# Footswitches.net
KiCad netlist of a schematic drawn in Altium Designer
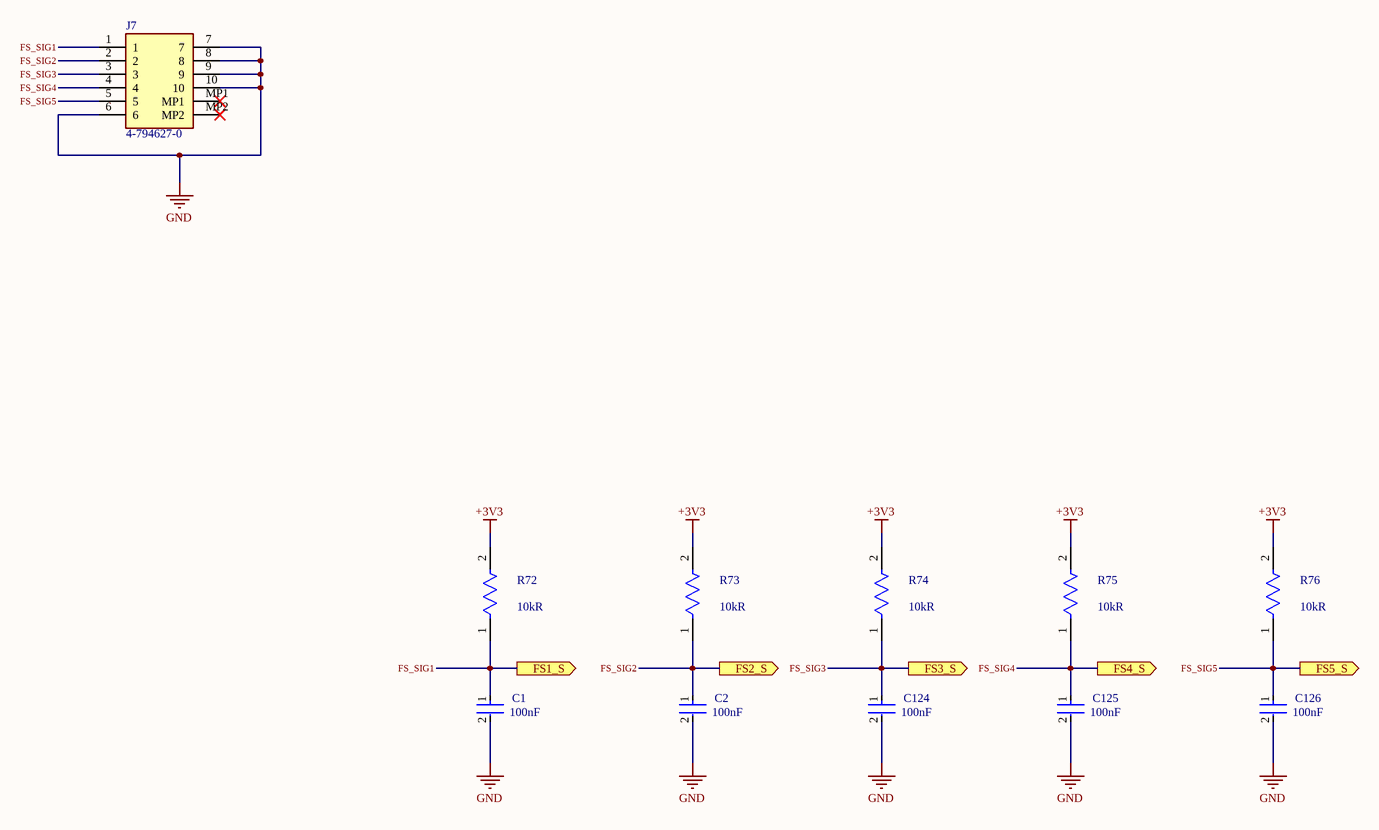
[diagram p0: Footswitches.SchDoc]

(export (version "E")
  (design (tool "Eeschema 10.0.6"))
  (components
    (comp (ref "C1")
      (value "GCM155R71H104ME02J")
      (footprint "FP-GCM155-0_05-IPC_A")
      (description "Ceramic Capacitor for Automotive 100nF ±20% 50VDC X7R 0402 Paper T/R")
      (fields (field (name "CAPACITANCE") "100nF"))
      (libsource (lib "Altium Content Vault") (part "02cd4be3c70576c341d710602a673aa"))
    )
    (comp (ref "C2")
      (value "GCM155R71H104ME02J")
      (footprint "FP-GCM155-0_05-IPC_A")
      (description "Ceramic Capacitor for Automotive 100nF ±20% 50VDC X7R 0402 Paper T/R")
      (fields (field (name "CAPACITANCE") "100nF"))
      (libsource (lib "Altium Content Vault") (part "02cd4be3c70576c341d710602a673aa"))
    )
    (comp (ref "C124")
      (value "GCM155R71H104ME02J")
      (footprint "FP-GCM155-0_05-IPC_A")
      (description "Ceramic Capacitor for Automotive 100nF ±20% 50VDC X7R 0402 Paper T/R")
      (fields (field (name "CAPACITANCE") "100nF"))
      (libsource (lib "Altium Content Vault") (part "02cd4be3c70576c341d710602a673aa"))
    )
    (comp (ref "C125")
      (value "GCM155R71H104ME02J")
      (footprint "FP-GCM155-0_05-IPC_A")
      (description "Ceramic Capacitor for Automotive 100nF ±20% 50VDC X7R 0402 Paper T/R")
      (fields (field (name "CAPACITANCE") "100nF"))
      (libsource (lib "Altium Content Vault") (part "02cd4be3c70576c341d710602a673aa"))
    )
    (comp (ref "C126")
      (value "GCM155R71H104ME02J")
      (footprint "FP-GCM155-0_05-IPC_A")
      (description "Ceramic Capacitor for Automotive 100nF ±20% 50VDC X7R 0402 Paper T/R")
      (fields (field (name "CAPACITANCE") "100nF"))
      (libsource (lib "Altium Content Vault") (part "02cd4be3c70576c341d710602a673aa"))
    )
    (comp (ref "J7")
      (value "4-794627-0")
      (footprint "SamacSys:47946270")
      (description "Connector")
      (fields (field (name "MOUSER PART NUMBER") "571-4-794627-0"))
      (libsource (lib "*") (part "4-794627-0"))
    )
    (comp (ref "R72")
      (value "RC0402FR-1310KL")
      (footprint "FP-RC0402-0_4-IPC_A")
      (description "RESISTOR 0402 10K 1%")
      (fields (field (name "RESISTANCE") "10kR") (field (name "TOLERANCE") "1%"))
      (libsource (lib "Altium Content Vault") (part "1029c3af85768c4190bb7ad29bc67b5"))
    )
    (comp (ref "R73")
      (value "RC0402FR-1310KL")
      (footprint "FP-RC0402-0_4-IPC_A")
      (description "RESISTOR 0402 10K 1%")
      (fields (field (name "RESISTANCE") "10kR") (field (name "TOLERANCE") "1%"))
      (libsource (lib "Altium Content Vault") (part "1029c3af85768c4190bb7ad29bc67b5"))
    )
    (comp (ref "R74")
      (value "RC0402FR-1310KL")
      (footprint "FP-RC0402-0_4-IPC_A")
      (description "RESISTOR 0402 10K 1%")
      (fields (field (name "RESISTANCE") "10kR") (field (name "TOLERANCE") "1%"))
      (libsource (lib "Altium Content Vault") (part "1029c3af85768c4190bb7ad29bc67b5"))
    )
    (comp (ref "R75")
      (value "RC0402FR-1310KL")
      (footprint "FP-RC0402-0_4-IPC_A")
      (description "RESISTOR 0402 10K 1%")
      (fields (field (name "RESISTANCE") "10kR") (field (name "TOLERANCE") "1%"))
      (libsource (lib "Altium Content Vault") (part "1029c3af85768c4190bb7ad29bc67b5"))
    )
    (comp (ref "R76")
      (value "RC0402FR-1310KL")
      (footprint "FP-RC0402-0_4-IPC_A")
      (description "RESISTOR 0402 10K 1%")
      (fields (field (name "RESISTANCE") "10kR") (field (name "TOLERANCE") "1%"))
      (libsource (lib "Altium Content Vault") (part "1029c3af85768c4190bb7ad29bc67b5"))
    )
  )
  (nets
    (net (code "1") (name "+3V3") (class "Default")
      (node (ref "R72") (pin "2") (pinfunction "2_2") (pintype "passive"))
      (node (ref "R73") (pin "2") (pinfunction "2_2") (pintype "passive"))
      (node (ref "R74") (pin "2") (pinfunction "2_2") (pintype "passive"))
      (node (ref "R75") (pin "2") (pinfunction "2_2") (pintype "passive"))
      (node (ref "R76") (pin "2") (pinfunction "2_2") (pintype "passive"))
    )
    (net (code "2") (name "/FS_SIG1") (class "Default")
      (node (ref "C1") (pin "1") (pinfunction "1_1") (pintype "passive"))
      (node (ref "J7") (pin "1") (pinfunction "1_1") (pintype "passive"))
      (node (ref "R72") (pin "1") (pinfunction "1_1") (pintype "passive"))
    )
    (net (code "3") (name "/FS_SIG2") (class "Default")
      (node (ref "C2") (pin "1") (pinfunction "1_1") (pintype "passive"))
      (node (ref "J7") (pin "2") (pinfunction "2_2") (pintype "passive"))
      (node (ref "R73") (pin "1") (pinfunction "1_1") (pintype "passive"))
    )
    (net (code "4") (name "/FS_SIG3") (class "Default")
      (node (ref "C124") (pin "1") (pinfunction "1_1") (pintype "passive"))
      (node (ref "J7") (pin "3") (pinfunction "3_3") (pintype "passive"))
      (node (ref "R74") (pin "1") (pinfunction "1_1") (pintype "passive"))
    )
    (net (code "5") (name "/FS_SIG4") (class "Default")
      (node (ref "C125") (pin "1") (pinfunction "1_1") (pintype "passive"))
      (node (ref "J7") (pin "4") (pinfunction "4_4") (pintype "passive"))
      (node (ref "R75") (pin "1") (pinfunction "1_1") (pintype "passive"))
    )
    (net (code "6") (name "/FS_SIG5") (class "Default")
      (node (ref "C126") (pin "1") (pinfunction "1_1") (pintype "passive"))
      (node (ref "J7") (pin "5") (pinfunction "5_5") (pintype "passive"))
      (node (ref "R76") (pin "1") (pinfunction "1_1") (pintype "passive"))
    )
    (net (code "7") (name "GND") (class "Default")
      (node (ref "C1") (pin "2") (pinfunction "2_2") (pintype "passive"))
      (node (ref "C124") (pin "2") (pinfunction "2_2") (pintype "passive"))
      (node (ref "C125") (pin "2") (pinfunction "2_2") (pintype "passive"))
      (node (ref "C126") (pin "2") (pinfunction "2_2") (pintype "passive"))
      (node (ref "C2") (pin "2") (pinfunction "2_2") (pintype "passive"))
      (node (ref "J7") (pin "10") (pinfunction "10_10") (pintype "passive"))
      (node (ref "J7") (pin "6") (pinfunction "6_6") (pintype "passive"))
      (node (ref "J7") (pin "7") (pinfunction "7_7") (pintype "passive"))
      (node (ref "J7") (pin "8") (pinfunction "8_8") (pintype "passive"))
      (node (ref "J7") (pin "9") (pinfunction "9_9") (pintype "passive"))
    )
    (net (code "8") (name "unconnected-(J7-PadMP1)") (class "Default")
      (node (ref "J7") (pin "MP1") (pinfunction "MP1_MP1") (pintype "passive+no_connect"))
    )
    (net (code "9") (name "unconnected-(J7-PadMP2)") (class "Default")
      (node (ref "J7") (pin "MP2") (pinfunction "MP2_MP2") (pintype "passive+no_connect"))
    )
  )
)
